# pitching_v3.net
KiCad netlist of a schematic drawn in EAGLE
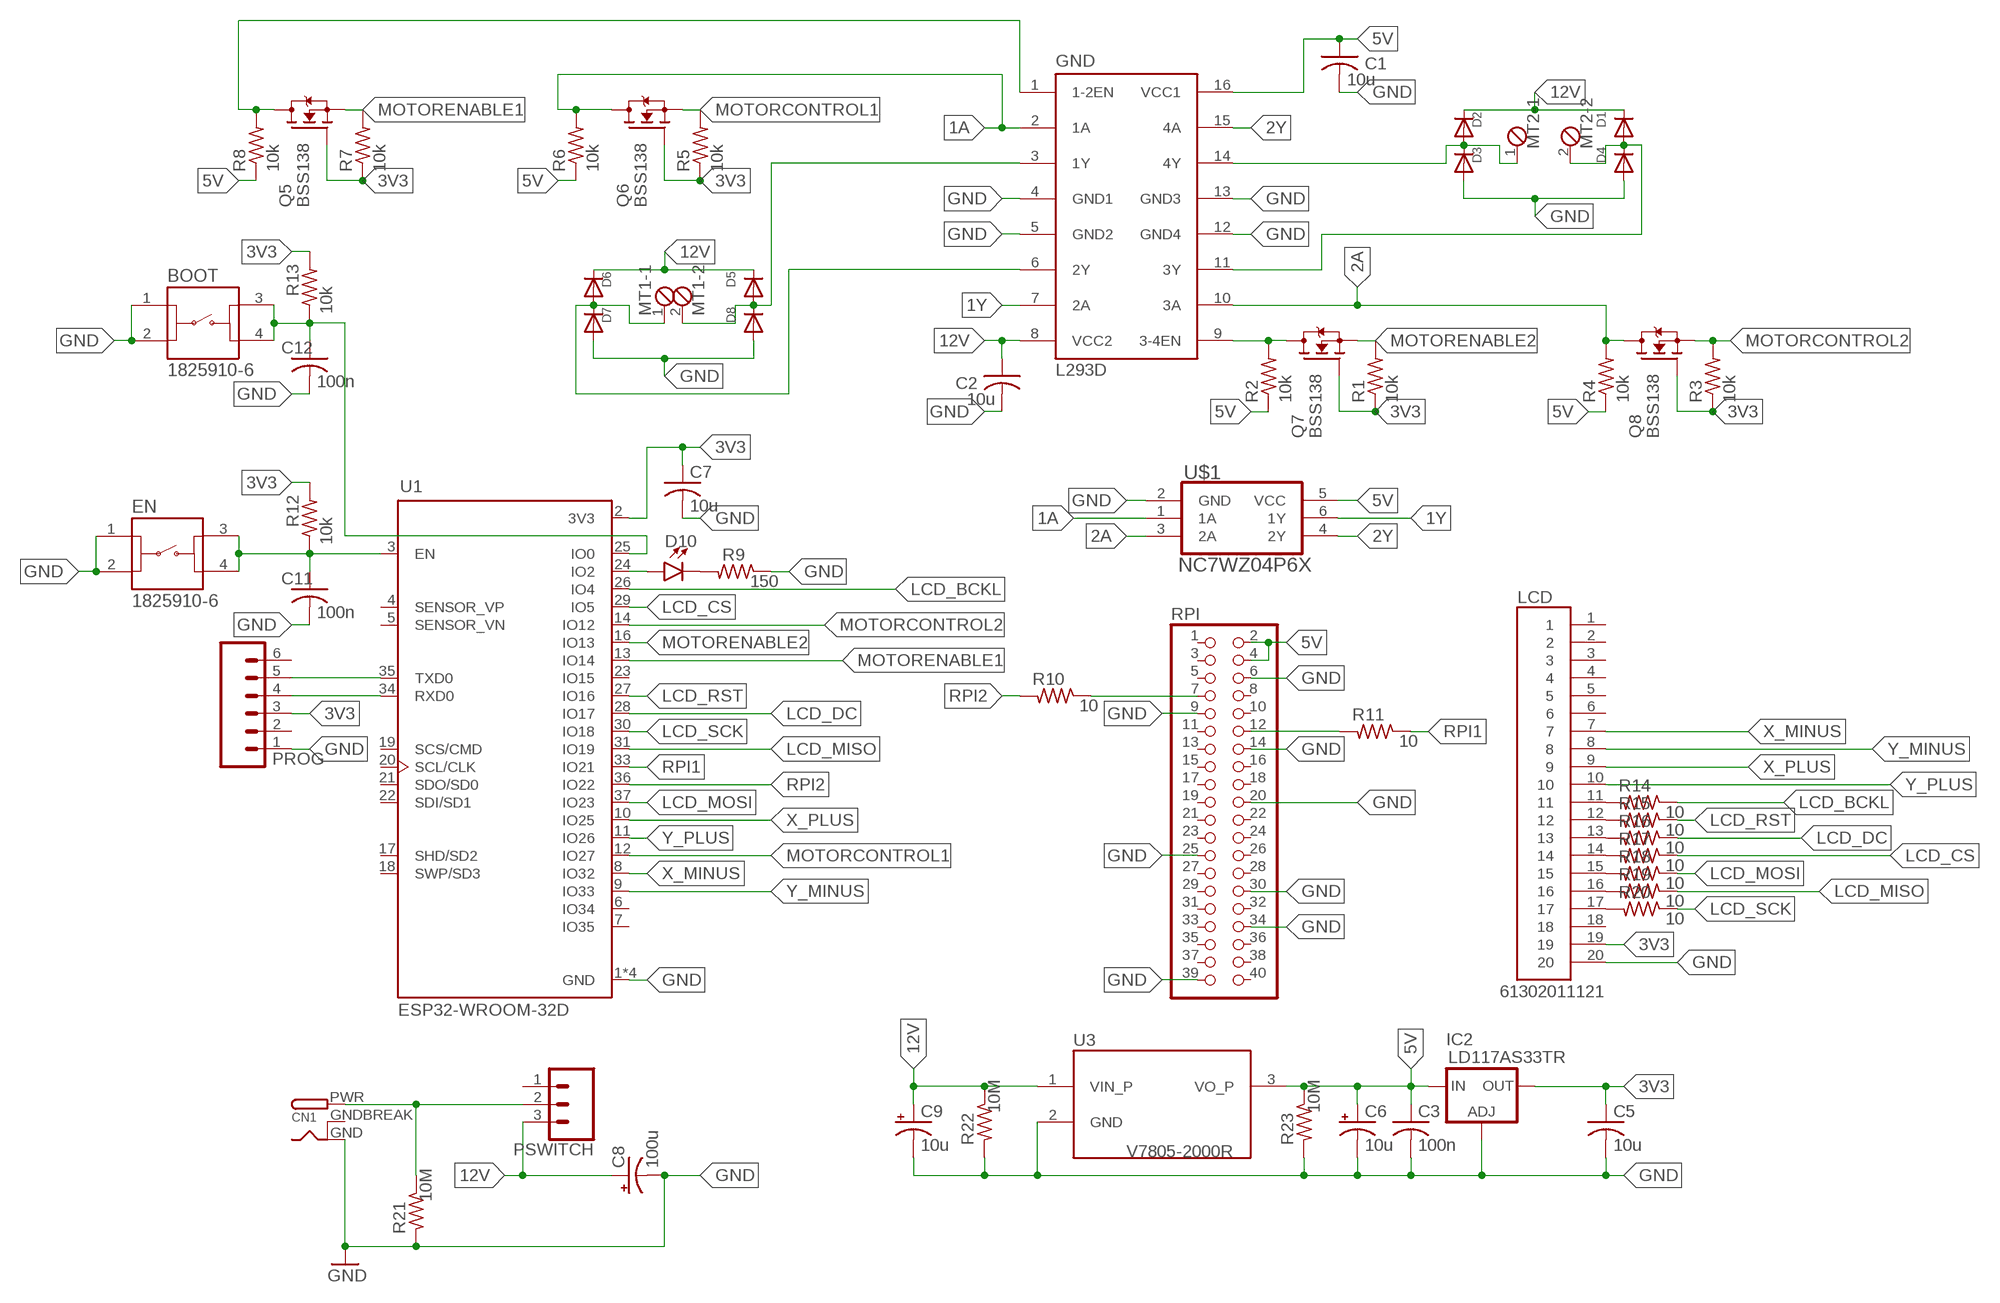
[diagram p0: schematic, sheet 1]

(export (version "E")
  (design (tool "Eeschema 10.0.6"))
  (components
    (comp (ref "BOOT")
      (value "1825910-6")
      (footprint "eagle-import:1825910-6")
      (fields
        (field (name "DIGIKEY_PART_NUMBER") "450-1650-ND")
        (field (name "MANUFACTURER") "TE Connectivity ALCOSWITCH Switches")
        (field (name "CREATED_BY") " PCBLayout.com")
      )
      (libsource (lib "eagle-import") (part "1825910-6"))
    )
    (comp (ref "C1")
      (value "10u")
      (footprint "eagle-import:C0805")
      (libsource (lib "eagle-import") (part "C-USC0805"))
    )
    (comp (ref "C2")
      (value "10u")
      (footprint "eagle-import:C0805")
      (libsource (lib "eagle-import") (part "C-USC0805"))
    )
    (comp (ref "C3")
      (value "100n")
      (footprint "eagle-import:C0805")
      (libsource (lib "eagle-import") (part "C-USC0805"))
    )
    (comp (ref "C5")
      (value "10u")
      (footprint "eagle-import:C0805")
      (libsource (lib "eagle-import") (part "C-USC0805"))
    )
    (comp (ref "C6")
      (value "10u")
      (footprint "eagle-import:153CLV-0405")
      (libsource (lib "eagle-import") (part "CPOL-US153CLV-0405"))
    )
    (comp (ref "C7")
      (value "10u")
      (footprint "eagle-import:C0805")
      (libsource (lib "eagle-import") (part "C-USC0805"))
    )
    (comp (ref "C8")
      (value "100u")
      (footprint "eagle-import:153CLV-0810")
      (libsource (lib "eagle-import") (part "CPOL-US153CLV-0810"))
    )
    (comp (ref "C9")
      (value "10u")
      (footprint "eagle-import:153CLV-0405")
      (libsource (lib "eagle-import") (part "CPOL-US153CLV-0405"))
    )
    (comp (ref "C11")
      (value "100n")
      (footprint "eagle-import:C0805")
      (libsource (lib "eagle-import") (part "C-USC0805"))
    )
    (comp (ref "C12")
      (value "100n")
      (footprint "eagle-import:C0805")
      (libsource (lib "eagle-import") (part "C-USC0805"))
    )
    (comp (ref "CN1")
      (value "DCBARRELPTH")
      (footprint "eagle-import:DCJACK_2MM_PTH")
      (libsource (lib "eagle-import") (part "DCBARRELPTH"))
    )
    (comp (ref "D1")
      (value "DIODESMA")
      (footprint "eagle-import:SMADIODE")
      (libsource (lib "eagle-import") (part "DIODESMA"))
    )
    (comp (ref "D2")
      (value "DIODESMA")
      (footprint "eagle-import:SMADIODE")
      (libsource (lib "eagle-import") (part "DIODESMA"))
    )
    (comp (ref "D3")
      (value "DIODESMA")
      (footprint "eagle-import:SMADIODE")
      (libsource (lib "eagle-import") (part "DIODESMA"))
    )
    (comp (ref "D4")
      (value "DIODESMA")
      (footprint "eagle-import:SMADIODE")
      (libsource (lib "eagle-import") (part "DIODESMA"))
    )
    (comp (ref "D5")
      (value "DIODESMA")
      (footprint "eagle-import:SMADIODE")
      (libsource (lib "eagle-import") (part "DIODESMA"))
    )
    (comp (ref "D6")
      (value "DIODESMA")
      (footprint "eagle-import:SMADIODE")
      (libsource (lib "eagle-import") (part "DIODESMA"))
    )
    (comp (ref "D7")
      (value "DIODESMA")
      (footprint "eagle-import:SMADIODE")
      (libsource (lib "eagle-import") (part "DIODESMA"))
    )
    (comp (ref "D8")
      (value "DIODESMA")
      (footprint "eagle-import:SMADIODE")
      (libsource (lib "eagle-import") (part "DIODESMA"))
    )
    (comp (ref "D10")
      (value "LED3MM")
      (footprint "eagle-import:LED_3MM")
      (libsource (lib "eagle-import") (part "LED3MM"))
    )
    (comp (ref "EN")
      (value "1825910-6")
      (footprint "eagle-import:1825910-6")
      (fields
        (field (name "DIGIKEY_PART_NUMBER") "450-1650-ND")
        (field (name "MANUFACTURER") "TE Connectivity ALCOSWITCH Switches")
        (field (name "CREATED_BY") " PCBLayout.com")
      )
      (libsource (lib "eagle-import") (part "1825910-6"))
    )
    (comp (ref "GND")
      (value "L293D")
      (footprint "eagle-import:DIL16")
      (libsource (lib "eagle-import") (part "L293D"))
    )
    (comp (ref "IC2")
      (value "LD117AS33TR")
      (footprint "eagle-import:SOT223")
      (libsource (lib "eagle-import") (part "LD117A?S33TR"))
    )
    (comp (ref "LCD")
      (value "61302011121")
      (footprint "eagle-import:61302011121")
      (fields
        (field (name "DIGIKEY_PART_NUMBER") "732-5329-ND")
        (field (name "MANUFACTURER") "Wurth Electronics Inc.")
        (field (name "CREATED_BY") "PCBLayout.com")
      )
      (libsource (lib "eagle-import") (part "61302011121"))
    )
    (comp (ref "MT1")
      (value "MPT2")
      (footprint "eagle-import:2POL254")
      (libsource (lib "eagle-import") (part "MPT2"))
    )
    (comp (ref "MT2")
      (value "MPT2")
      (footprint "eagle-import:2POL254")
      (libsource (lib "eagle-import") (part "MPT2"))
    )
    (comp (ref "PROG")
      (value "CONN_06SILK_FEMALE_PTH")
      (footprint "eagle-import:1X06")
      (libsource (lib "eagle-import") (part "CONN_06SILK_FEMALE_PTH"))
    )
    (comp (ref "PSWITCH")
      (value "CONN_03")
      (footprint "eagle-import:1X03")
      (libsource (lib "eagle-import") (part "CONN_03"))
    )
    (comp (ref "Q5")
      (value "BSS138")
      (footprint "eagle-import:SOT23")
      (fields (field (name "MF") "Fairchild"))
      (libsource (lib "eagle-import") (part "BSS138"))
    )
    (comp (ref "Q6")
      (value "BSS138")
      (footprint "eagle-import:SOT23")
      (fields (field (name "MF") "Fairchild"))
      (libsource (lib "eagle-import") (part "BSS138"))
    )
    (comp (ref "Q7")
      (value "BSS138")
      (footprint "eagle-import:SOT23")
      (fields (field (name "MF") "Fairchild"))
      (libsource (lib "eagle-import") (part "BSS138"))
    )
    (comp (ref "Q8")
      (value "BSS138")
      (footprint "eagle-import:SOT23")
      (fields (field (name "MF") "Fairchild"))
      (libsource (lib "eagle-import") (part "BSS138"))
    )
    (comp (ref "R1")
      (value "10k")
      (footprint "eagle-import:R0805")
      (libsource (lib "eagle-import") (part "R-US_R0805"))
    )
    (comp (ref "R2")
      (value "10k")
      (footprint "eagle-import:R0805")
      (libsource (lib "eagle-import") (part "R-US_R0805"))
    )
    (comp (ref "R3")
      (value "10k")
      (footprint "eagle-import:R0805")
      (libsource (lib "eagle-import") (part "R-US_R0805"))
    )
    (comp (ref "R4")
      (value "10k")
      (footprint "eagle-import:R0805")
      (libsource (lib "eagle-import") (part "R-US_R0805"))
    )
    (comp (ref "R5")
      (value "10k")
      (footprint "eagle-import:R0805")
      (libsource (lib "eagle-import") (part "R-US_R0805"))
    )
    (comp (ref "R6")
      (value "10k")
      (footprint "eagle-import:R0805")
      (libsource (lib "eagle-import") (part "R-US_R0805"))
    )
    (comp (ref "R7")
      (value "10k")
      (footprint "eagle-import:R0805")
      (libsource (lib "eagle-import") (part "R-US_R0805"))
    )
    (comp (ref "R8")
      (value "10k")
      (footprint "eagle-import:R0805")
      (libsource (lib "eagle-import") (part "R-US_R0805"))
    )
    (comp (ref "R9")
      (value "150")
      (footprint "eagle-import:R0805")
      (libsource (lib "eagle-import") (part "R-US_R0805"))
    )
    (comp (ref "R10")
      (value "10")
      (footprint "eagle-import:R0805")
      (libsource (lib "eagle-import") (part "R-US_R0805"))
    )
    (comp (ref "R11")
      (value "10")
      (footprint "eagle-import:R0805")
      (libsource (lib "eagle-import") (part "R-US_R0805"))
    )
    (comp (ref "R12")
      (value "10k")
      (footprint "eagle-import:R0805")
      (libsource (lib "eagle-import") (part "R-US_R0805"))
    )
    (comp (ref "R13")
      (value "10k")
      (footprint "eagle-import:R0805")
      (libsource (lib "eagle-import") (part "R-US_R0805"))
    )
    (comp (ref "R14")
      (value "10")
      (footprint "eagle-import:R0805")
      (libsource (lib "eagle-import") (part "R-US_R0805"))
    )
    (comp (ref "R15")
      (value "10")
      (footprint "eagle-import:R0805")
      (libsource (lib "eagle-import") (part "R-US_R0805"))
    )
    (comp (ref "R16")
      (value "10")
      (footprint "eagle-import:R0805")
      (libsource (lib "eagle-import") (part "R-US_R0805"))
    )
    (comp (ref "R17")
      (value "10")
      (footprint "eagle-import:R0805")
      (libsource (lib "eagle-import") (part "R-US_R0805"))
    )
    (comp (ref "R18")
      (value "10")
      (footprint "eagle-import:R0805")
      (libsource (lib "eagle-import") (part "R-US_R0805"))
    )
    (comp (ref "R19")
      (value "10")
      (footprint "eagle-import:R0805")
      (libsource (lib "eagle-import") (part "R-US_R0805"))
    )
    (comp (ref "R20")
      (value "10")
      (footprint "eagle-import:R0805")
      (libsource (lib "eagle-import") (part "R-US_R0805"))
    )
    (comp (ref "R21")
      (value "10M")
      (footprint "eagle-import:R1206")
      (libsource (lib "eagle-import") (part "R-US_R1206"))
    )
    (comp (ref "R22")
      (value "10M")
      (footprint "eagle-import:R1206")
      (libsource (lib "eagle-import") (part "R-US_R1206"))
    )
    (comp (ref "R23")
      (value "10M")
      (footprint "eagle-import:R1206")
      (libsource (lib "eagle-import") (part "R-US_R1206"))
    )
    (comp (ref "RPI")
      (value "PINHD-2X20")
      (footprint "eagle-import:2X20")
      (libsource (lib "eagle-import") (part "PINHD-2X20"))
    )
    (comp (ref "U$1")
      (value "NC7WZ04P6X")
      (footprint "eagle-import:SOT65P210X110-6N")
      (libsource (lib "eagle-import") (part "NC7WZ04P6X"))
    )
    (comp (ref "U1")
      (value "ESP32-WROOM-32D")
      (footprint "eagle-import:MODULE_ESP32-WROOM-32D")
      (fields (field (name "MF") "Espressif Systems"))
      (libsource (lib "eagle-import") (part "ESP32-WROOM-32D"))
    )
    (comp (ref "U3")
      (value "V7805-2000R")
      (footprint "eagle-import:CONV_V7805-2000R")
      (fields (field (name "MANUFACTURER") "CUI INC"))
      (libsource (lib "eagle-import") (part "V7805-2000R"))
    )
  )
  (nets
    (net (code "1") (name "/GNDBREAK") (class "Default")
      (node (ref "CN1") (pin "GNDBREAK") (pinfunction "GNDBREAK_GNDBREAK") (pintype "power_in"))
    )
    (net (code "2") (name "1A") (class "Default")
      (node (ref "GND") (pin "2") (pinfunction "1A_2") (pintype "input"))
      (node (ref "Q6") (pin "3") (pinfunction "D_3") (pintype "passive"))
      (node (ref "R6") (pin "2") (pinfunction "2_2") (pintype "passive"))
      (node (ref "U$1") (pin "1") (pinfunction "1A_1") (pintype "passive"))
    )
    (net (code "3") (name "1Y") (class "Default")
      (node (ref "GND") (pin "7") (pinfunction "2A_7") (pintype "input"))
      (node (ref "U$1") (pin "6") (pinfunction "1Y_6") (pintype "passive"))
    )
    (net (code "4") (name "2A") (class "Default")
      (node (ref "GND") (pin "10") (pinfunction "3A_10") (pintype "input"))
      (node (ref "Q8") (pin "3") (pinfunction "D_3") (pintype "passive"))
      (node (ref "R4") (pin "2") (pinfunction "2_2") (pintype "passive"))
      (node (ref "U$1") (pin "3") (pinfunction "2A_3") (pintype "passive"))
    )
    (net (code "5") (name "2Y") (class "Default")
      (node (ref "GND") (pin "15") (pinfunction "4A_15") (pintype "input"))
      (node (ref "U$1") (pin "4") (pinfunction "2Y_4") (pintype "passive"))
    )
    (net (code "6") (name "3V3") (class "Default")
      (node (ref "C5") (pin "1") (pinfunction "1_1") (pintype "passive"))
      (node (ref "C7") (pin "1") (pinfunction "1_1") (pintype "passive"))
      (node (ref "IC2") (pin "4") (pinfunction "OUT_4") (pintype "passive"))
      (node (ref "LCD") (pin "19") (pinfunction "19_19") (pintype "passive"))
      (node (ref "PROG") (pin "3") (pinfunction "3_3") (pintype "passive"))
      (node (ref "Q5") (pin "1") (pinfunction "G_1") (pintype "passive"))
      (node (ref "Q6") (pin "1") (pinfunction "G_1") (pintype "passive"))
      (node (ref "Q7") (pin "1") (pinfunction "G_1") (pintype "passive"))
      (node (ref "Q8") (pin "1") (pinfunction "G_1") (pintype "passive"))
      (node (ref "R1") (pin "1") (pinfunction "1_1") (pintype "passive"))
      (node (ref "R12") (pin "2") (pinfunction "2_2") (pintype "passive"))
      (node (ref "R13") (pin "2") (pinfunction "2_2") (pintype "passive"))
      (node (ref "R3") (pin "1") (pinfunction "1_1") (pintype "passive"))
      (node (ref "R5") (pin "1") (pinfunction "1_1") (pintype "passive"))
      (node (ref "R7") (pin "1") (pinfunction "1_1") (pintype "passive"))
      (node (ref "U1") (pin "2") (pinfunction "3V3_2") (pintype "power_in"))
    )
    (net (code "7") (name "5V") (class "Default")
      (node (ref "C1") (pin "1") (pinfunction "1_1") (pintype "passive"))
      (node (ref "C3") (pin "1") (pinfunction "1_1") (pintype "passive"))
      (node (ref "C6") (pin "+") (pinfunction "+_+") (pintype "passive"))
      (node (ref "GND") (pin "16") (pinfunction "VCC1_16") (pintype "power_in"))
      (node (ref "IC2") (pin "3") (pinfunction "IN_3") (pintype "input"))
      (node (ref "R2") (pin "1") (pinfunction "1_1") (pintype "passive"))
      (node (ref "R23") (pin "1") (pinfunction "1_1") (pintype "passive"))
      (node (ref "R4") (pin "1") (pinfunction "1_1") (pintype "passive"))
      (node (ref "R6") (pin "1") (pinfunction "1_1") (pintype "passive"))
      (node (ref "R8") (pin "1") (pinfunction "1_1") (pintype "passive"))
      (node (ref "RPI") (pin "2") (pinfunction "2_2") (pintype "passive"))
      (node (ref "RPI") (pin "4") (pinfunction "4_4") (pintype "passive"))
      (node (ref "U$1") (pin "5") (pinfunction "VCC_5") (pintype "passive"))
      (node (ref "U3") (pin "3") (pinfunction "VO_P_3") (pintype "output"))
    )
    (net (code "8") (name "12V") (class "Default")
      (node (ref "C2") (pin "1") (pinfunction "1_1") (pintype "passive"))
      (node (ref "C8") (pin "+") (pinfunction "+_+") (pintype "passive"))
      (node (ref "C9") (pin "+") (pinfunction "+_+") (pintype "passive"))
      (node (ref "D1") (pin "C") (pinfunction "C_C") (pintype "passive"))
      (node (ref "D2") (pin "C") (pinfunction "C_C") (pintype "passive"))
      (node (ref "D5") (pin "C") (pinfunction "C_C") (pintype "passive"))
      (node (ref "D6") (pin "C") (pinfunction "C_C") (pintype "passive"))
      (node (ref "GND") (pin "8") (pinfunction "VCC2_8") (pintype "power_in"))
      (node (ref "PSWITCH") (pin "3") (pinfunction "3_3") (pintype "passive"))
      (node (ref "R22") (pin "1") (pinfunction "1_1") (pintype "passive"))
      (node (ref "U3") (pin "1") (pinfunction "VIN_P_1") (pintype "input"))
    )
    (net (code "9") (name "GND") (class "Default")
      (node (ref "BOOT") (pin "1") (pinfunction "1_1") (pintype "passive"))
      (node (ref "BOOT") (pin "2") (pinfunction "2_2") (pintype "passive"))
      (node (ref "C1") (pin "2") (pinfunction "2_2") (pintype "passive"))
      (node (ref "C11") (pin "2") (pinfunction "2_2") (pintype "passive"))
      (node (ref "C12") (pin "2") (pinfunction "2_2") (pintype "passive"))
      (node (ref "C2") (pin "2") (pinfunction "2_2") (pintype "passive"))
      (node (ref "C3") (pin "2") (pinfunction "2_2") (pintype "passive"))
      (node (ref "C5") (pin "2") (pinfunction "2_2") (pintype "passive"))
      (node (ref "C6") (pin "-") (pinfunction "-_-") (pintype "passive"))
      (node (ref "C7") (pin "2") (pinfunction "2_2") (pintype "passive"))
      (node (ref "C8") (pin "-") (pinfunction "-_-") (pintype "passive"))
      (node (ref "C9") (pin "-") (pinfunction "-_-") (pintype "passive"))
      (node (ref "CN1") (pin "GND") (pinfunction "GND_GND") (pintype "power_in"))
      (node (ref "D3") (pin "A") (pinfunction "A_A") (pintype "passive"))
      (node (ref "D4") (pin "A") (pinfunction "A_A") (pintype "passive"))
      (node (ref "D7") (pin "A") (pinfunction "A_A") (pintype "passive"))
      (node (ref "D8") (pin "A") (pinfunction "A_A") (pintype "passive"))
      (node (ref "EN") (pin "1") (pinfunction "1_1") (pintype "passive"))
      (node (ref "EN") (pin "2") (pinfunction "2_2") (pintype "passive"))
      (node (ref "GND") (pin "12") (pinfunction "GND4_12") (pintype "power_in"))
      (node (ref "GND") (pin "13") (pinfunction "GND3_13") (pintype "power_in"))
      (node (ref "GND") (pin "4") (pinfunction "GND1_4") (pintype "power_in"))
      (node (ref "GND") (pin "5") (pinfunction "GND2_5") (pintype "power_in"))
      (node (ref "IC2") (pin "1") (pinfunction "ADJ_1") (pintype "input"))
      (node (ref "LCD") (pin "20") (pinfunction "20_20") (pintype "passive"))
      (node (ref "PROG") (pin "1") (pinfunction "1_1") (pintype "passive"))
      (node (ref "R21") (pin "2") (pinfunction "2_2") (pintype "passive"))
      (node (ref "R22") (pin "2") (pinfunction "2_2") (pintype "passive"))
      (node (ref "R23") (pin "2") (pinfunction "2_2") (pintype "passive"))
      (node (ref "R9") (pin "1") (pinfunction "1_1") (pintype "passive"))
      (node (ref "RPI") (pin "14") (pinfunction "14_14") (pintype "passive"))
      (node (ref "RPI") (pin "20") (pinfunction "20_20") (pintype "passive"))
      (node (ref "RPI") (pin "25") (pinfunction "25_25") (pintype "passive"))
      (node (ref "RPI") (pin "30") (pinfunction "30_30") (pintype "passive"))
      (node (ref "RPI") (pin "34") (pinfunction "34_34") (pintype "passive"))
      (node (ref "RPI") (pin "39") (pinfunction "39_39") (pintype "passive"))
      (node (ref "RPI") (pin "6") (pinfunction "6_6") (pintype "passive"))
      (node (ref "RPI") (pin "9") (pinfunction "9_9") (pintype "passive"))
      (node (ref "U$1") (pin "2") (pinfunction "GND_2") (pintype "passive"))
      (node (ref "U1") (pin "1") (pinfunction "GND_1") (pintype "power_in"))
      (node (ref "U1") (pin "15") (pinfunction "GND_15") (pintype "power_in"))
      (node (ref "U1") (pin "38") (pinfunction "GND_38") (pintype "power_in"))
      (node (ref "U1") (pin "39") (pinfunction "GND_39") (pintype "power_in"))
      (node (ref "U3") (pin "2") (pinfunction "GND_2") (pintype "power_in"))
    )
    (net (code "10") (name "LCD_BCKL") (class "Default")
      (node (ref "R14") (pin "1") (pinfunction "1_1") (pintype "passive"))
      (node (ref "U1") (pin "26") (pinfunction "IO4_26") (pintype "bidirectional"))
    )
    (net (code "11") (name "LCD_CS") (class "Default")
      (node (ref "R17") (pin "1") (pinfunction "1_1") (pintype "passive"))
      (node (ref "U1") (pin "29") (pinfunction "IO5_29") (pintype "bidirectional"))
    )
    (net (code "12") (name "LCD_DC") (class "Default")
      (node (ref "R16") (pin "1") (pinfunction "1_1") (pintype "passive"))
      (node (ref "U1") (pin "28") (pinfunction "IO17_28") (pintype "bidirectional"))
    )
    (net (code "13") (name "LCD_MISO") (class "Default")
      (node (ref "R19") (pin "1") (pinfunction "1_1") (pintype "passive"))
      (node (ref "U1") (pin "31") (pinfunction "IO19_31") (pintype "bidirectional"))
    )
    (net (code "14") (name "LCD_MOSI") (class "Default")
      (node (ref "R18") (pin "1") (pinfunction "1_1") (pintype "passive"))
      (node (ref "U1") (pin "37") (pinfunction "IO23_37") (pintype "bidirectional"))
    )
    (net (code "15") (name "LCD_RST") (class "Default")
      (node (ref "R15") (pin "1") (pinfunction "1_1") (pintype "passive"))
      (node (ref "U1") (pin "27") (pinfunction "IO16_27") (pintype "bidirectional"))
    )
    (net (code "16") (name "LCD_SCK") (class "Default")
      (node (ref "R20") (pin "1") (pinfunction "1_1") (pintype "passive"))
      (node (ref "U1") (pin "30") (pinfunction "IO18_30") (pintype "bidirectional"))
    )
    (net (code "17") (name "MOTORCONTROL1") (class "Default")
      (node (ref "Q6") (pin "2") (pinfunction "S_2") (pintype "passive"))
      (node (ref "R5") (pin "2") (pinfunction "2_2") (pintype "passive"))
      (node (ref "U1") (pin "12") (pinfunction "IO27_12") (pintype "bidirectional"))
    )
    (net (code "18") (name "MOTORCONTROL2") (class "Default")
      (node (ref "Q8") (pin "2") (pinfunction "S_2") (pintype "passive"))
      (node (ref "R3") (pin "2") (pinfunction "2_2") (pintype "passive"))
      (node (ref "U1") (pin "14") (pinfunction "IO12_14") (pintype "bidirectional"))
    )
    (net (code "19") (name "MOTORENABLE1") (class "Default")
      (node (ref "Q5") (pin "2") (pinfunction "S_2") (pintype "passive"))
      (node (ref "R7") (pin "2") (pinfunction "2_2") (pintype "passive"))
      (node (ref "U1") (pin "13") (pinfunction "IO14_13") (pintype "bidirectional"))
    )
    (net (code "20") (name "MOTORENABLE2") (class "Default")
      (node (ref "Q7") (pin "2") (pinfunction "S_2") (pintype "passive"))
      (node (ref "R1") (pin "2") (pinfunction "2_2") (pintype "passive"))
      (node (ref "U1") (pin "16") (pinfunction "IO13_16") (pintype "bidirectional"))
    )
    (net (code "21") (name "Net-(CN1-PadPWR)") (class "Default")
      (node (ref "CN1") (pin "PWR") (pinfunction "PWR_PWR") (pintype "power_in"))
      (node (ref "PSWITCH") (pin "2") (pinfunction "2_2") (pintype "passive"))
      (node (ref "R21") (pin "1") (pinfunction "1_1") (pintype "passive"))
    )
    (net (code "22") (name "Net-(D10-C)") (class "Default")
      (node (ref "D10") (pin "K") (pinfunction "C_K") (pintype "passive"))
      (node (ref "R9") (pin "2") (pinfunction "2_2") (pintype "passive"))
    )
    (net (code "23") (name "Net-(GND-1-2EN)") (class "Default")
      (node (ref "GND") (pin "1") (pinfunction "1-2EN_1") (pintype "input"))
      (node (ref "Q5") (pin "3") (pinfunction "D_3") (pintype "passive"))
      (node (ref "R8") (pin "2") (pinfunction "2_2") (pintype "passive"))
    )
    (net (code "24") (name "Net-(GND-1Y)") (class "Default")
      (node (ref "D5") (pin "A") (pinfunction "A_A") (pintype "passive"))
      (node (ref "D8") (pin "C") (pinfunction "C_C") (pintype "passive"))
      (node (ref "GND") (pin "3") (pinfunction "1Y_3") (pintype "output"))
      (node (ref "MT1") (pin "2") (pinfunction "1_2") (pintype "passive"))
    )
    (net (code "25") (name "Net-(GND-2Y)") (class "Default")
      (node (ref "D6") (pin "A") (pinfunction "A_A") (pintype "passive"))
      (node (ref "D7") (pin "C") (pinfunction "C_C") (pintype "passive"))
      (node (ref "GND") (pin "6") (pinfunction "2Y_6") (pintype "output"))
      (node (ref "MT1") (pin "1") (pinfunction "1_1") (pintype "passive"))
    )
    (net (code "26") (name "Net-(GND-3-4EN)") (class "Default")
      (node (ref "GND") (pin "9") (pinfunction "3-4EN_9") (pintype "input"))
      (node (ref "Q7") (pin "3") (pinfunction "D_3") (pintype "passive"))
      (node (ref "R2") (pin "2") (pinfunction "2_2") (pintype "passive"))
    )
    (net (code "27") (name "Net-(GND-3Y)") (class "Default")
      (node (ref "D1") (pin "A") (pinfunction "A_A") (pintype "passive"))
      (node (ref "D4") (pin "C") (pinfunction "C_C") (pintype "passive"))
      (node (ref "GND") (pin "11") (pinfunction "3Y_11") (pintype "output"))
      (node (ref "MT2") (pin "2") (pinfunction "1_2") (pintype "passive"))
    )
    (net (code "28") (name "Net-(GND-4Y)") (class "Default")
      (node (ref "D2") (pin "A") (pinfunction "A_A") (pintype "passive"))
      (node (ref "D3") (pin "C") (pinfunction "C_C") (pintype "passive"))
      (node (ref "GND") (pin "14") (pinfunction "4Y_14") (pintype "output"))
      (node (ref "MT2") (pin "1") (pinfunction "1_1") (pintype "passive"))
    )
    (net (code "29") (name "Net-(LCD-Pad11)") (class "Default")
      (node (ref "LCD") (pin "11") (pinfunction "11_11") (pintype "passive"))
      (node (ref "R14") (pin "2") (pinfunction "2_2") (pintype "passive"))
    )
    (net (code "30") (name "Net-(LCD-Pad12)") (class "Default")
      (node (ref "LCD") (pin "12") (pinfunction "12_12") (pintype "passive"))
      (node (ref "R15") (pin "2") (pinfunction "2_2") (pintype "passive"))
    )
    (net (code "31") (name "Net-(LCD-Pad13)") (class "Default")
      (node (ref "LCD") (pin "13") (pinfunction "13_13") (pintype "passive"))
      (node (ref "R16") (pin "2") (pinfunction "2_2") (pintype "passive"))
    )
    (net (code "32") (name "Net-(LCD-Pad14)") (class "Default")
      (node (ref "LCD") (pin "14") (pinfunction "14_14") (pintype "passive"))
      (node (ref "R17") (pin "2") (pinfunction "2_2") (pintype "passive"))
    )
    (net (code "33") (name "Net-(LCD-Pad15)") (class "Default")
      (node (ref "LCD") (pin "15") (pinfunction "15_15") (pintype "passive"))
      (node (ref "R18") (pin "2") (pinfunction "2_2") (pintype "passive"))
    )
    (net (code "34") (name "Net-(LCD-Pad16)") (class "Default")
      (node (ref "LCD") (pin "16") (pinfunction "16_16") (pintype "passive"))
      (node (ref "R19") (pin "2") (pinfunction "2_2") (pintype "passive"))
    )
    (net (code "35") (name "Net-(LCD-Pad17)") (class "Default")
      (node (ref "LCD") (pin "17") (pinfunction "17_17") (pintype "passive"))
      (node (ref "R20") (pin "2") (pinfunction "2_2") (pintype "passive"))
    )
    (net (code "36") (name "Net-(R10-Pad1)") (class "Default")
      (node (ref "R10") (pin "1") (pinfunction "1_1") (pintype "passive"))
      (node (ref "RPI") (pin "7") (pinfunction "7_7") (pintype "passive"))
    )
    (net (code "37") (name "Net-(R11-Pad2)") (class "Default")
      (node (ref "R11") (pin "2") (pinfunction "2_2") (pintype "passive"))
      (node (ref "RPI") (pin "12") (pinfunction "12_12") (pintype "passive"))
    )
    (net (code "38") (name "Net-(U1-EN)") (class "Default")
      (node (ref "C11") (pin "1") (pinfunction "1_1") (pintype "passive"))
      (node (ref "EN") (pin "3") (pinfunction "3_3") (pintype "passive"))
      (node (ref "EN") (pin "4") (pinfunction "4_4") (pintype "passive"))
      (node (ref "R12") (pin "1") (pinfunction "1_1") (pintype "passive"))
      (node (ref "U1") (pin "3") (pinfunction "EN_3") (pintype "input"))
    )
    (net (code "39") (name "Net-(U1-IO0)") (class "Default")
      (node (ref "BOOT") (pin "3") (pinfunction "3_3") (pintype "passive"))
      (node (ref "BOOT") (pin "4") (pinfunction "4_4") (pintype "passive"))
      (node (ref "C12") (pin "1") (pinfunction "1_1") (pintype "passive"))
      (node (ref "R13") (pin "1") (pinfunction "1_1") (pintype "passive"))
      (node (ref "U1") (pin "25") (pinfunction "IO0_25") (pintype "bidirectional"))
    )
    (net (code "40") (name "Net-(U1-IO2)") (class "Default")
      (node (ref "D10") (pin "A") (pinfunction "A_A") (pintype "passive"))
      (node (ref "U1") (pin "24") (pinfunction "IO2_24") (pintype "bidirectional"))
    )
    (net (code "41") (name "Net-(U1-RXD0)") (class "Default")
      (node (ref "PROG") (pin "4") (pinfunction "4_4") (pintype "passive"))
      (node (ref "U1") (pin "34") (pinfunction "RXD0_34") (pintype "bidirectional"))
    )
    (net (code "42") (name "Net-(U1-TXD0)") (class "Default")
      (node (ref "PROG") (pin "5") (pinfunction "5_5") (pintype "passive"))
      (node (ref "U1") (pin "35") (pinfunction "TXD0_35") (pintype "bidirectional"))
    )
    (net (code "43") (name "RPI1") (class "Default")
      (node (ref "R11") (pin "1") (pinfunction "1_1") (pintype "passive"))
      (node (ref "U1") (pin "33") (pinfunction "IO21_33") (pintype "bidirectional"))
    )
    (net (code "44") (name "RPI2") (class "Default")
      (node (ref "R10") (pin "2") (pinfunction "2_2") (pintype "passive"))
      (node (ref "U1") (pin "36") (pinfunction "IO22_36") (pintype "bidirectional"))
    )
    (net (code "45") (name "X_MINUS") (class "Default")
      (node (ref "LCD") (pin "7") (pinfunction "7_7") (pintype "passive"))
      (node (ref "U1") (pin "8") (pinfunction "IO32_8") (pintype "bidirectional"))
    )
    (net (code "46") (name "X_PLUS") (class "Default")
      (node (ref "LCD") (pin "9") (pinfunction "9_9") (pintype "passive"))
      (node (ref "U1") (pin "10") (pinfunction "IO25_10") (pintype "bidirectional"))
    )
    (net (code "47") (name "Y_MINUS") (class "Default")
      (node (ref "LCD") (pin "8") (pinfunction "8_8") (pintype "passive"))
      (node (ref "U1") (pin "9") (pinfunction "IO33_9") (pintype "bidirectional"))
    )
    (net (code "48") (name "Y_PLUS") (class "Default")
      (node (ref "LCD") (pin "10") (pinfunction "10_10") (pintype "passive"))
      (node (ref "U1") (pin "11") (pinfunction "IO26_11") (pintype "bidirectional"))
    )
    (net (code "49") (name "unconnected-(LCD-Pad1)") (class "Default")
      (node (ref "LCD") (pin "1") (pinfunction "1_1") (pintype "passive"))
    )
    (net (code "50") (name "unconnected-(LCD-Pad2)") (class "Default")
      (node (ref "LCD") (pin "2") (pinfunction "2_2") (pintype "passive"))
    )
    (net (code "51") (name "unconnected-(LCD-Pad3)") (class "Default")
      (node (ref "LCD") (pin "3") (pinfunction "3_3") (pintype "passive"))
    )
    (net (code "52") (name "unconnected-(LCD-Pad4)") (class "Default")
      (node (ref "LCD") (pin "4") (pinfunction "4_4") (pintype "passive"))
    )
    (net (code "53") (name "unconnected-(LCD-Pad5)") (class "Default")
      (node (ref "LCD") (pin "5") (pinfunction "5_5") (pintype "passive"))
    )
    (net (code "54") (name "unconnected-(LCD-Pad6)") (class "Default")
      (node (ref "LCD") (pin "6") (pinfunction "6_6") (pintype "passive"))
    )
    (net (code "55") (name "unconnected-(LCD-Pad18)") (class "Default")
      (node (ref "LCD") (pin "18") (pinfunction "18_18") (pintype "passive"))
    )
    (net (code "56") (name "unconnected-(PROG-Pad2)") (class "Default")
      (node (ref "PROG") (pin "2") (pinfunction "2_2") (pintype "passive"))
    )
    (net (code "57") (name "unconnected-(PROG-Pad6)") (class "Default")
      (node (ref "PROG") (pin "6") (pinfunction "6_6") (pintype "passive"))
    )
    (net (code "58") (name "unconnected-(PSWITCH-Pad1)") (class "Default")
      (node (ref "PSWITCH") (pin "1") (pinfunction "1_1") (pintype "passive"))
    )
    (net (code "59") (name "unconnected-(RPI-Pad1)") (class "Default")
      (node (ref "RPI") (pin "1") (pinfunction "1_1") (pintype "passive"))
    )
    (net (code "60") (name "unconnected-(RPI-Pad3)") (class "Default")
      (node (ref "RPI") (pin "3") (pinfunction "3_3") (pintype "passive"))
    )
    (net (code "61") (name "unconnected-(RPI-Pad5)") (class "Default")
      (node (ref "RPI") (pin "5") (pinfunction "5_5") (pintype "passive"))
    )
    (net (code "62") (name "unconnected-(RPI-Pad8)") (class "Default")
      (node (ref "RPI") (pin "8") (pinfunction "8_8") (pintype "passive"))
    )
    (net (code "63") (name "unconnected-(RPI-Pad10)") (class "Default")
      (node (ref "RPI") (pin "10") (pinfunction "10_10") (pintype "passive"))
    )
    (net (code "64") (name "unconnected-(RPI-Pad11)") (class "Default")
      (node (ref "RPI") (pin "11") (pinfunction "11_11") (pintype "passive"))
    )
    (net (code "65") (name "unconnected-(RPI-Pad13)") (class "Default")
      (node (ref "RPI") (pin "13") (pinfunction "13_13") (pintype "passive"))
    )
    (net (code "66") (name "unconnected-(RPI-Pad15)") (class "Default")
      (node (ref "RPI") (pin "15") (pinfunction "15_15") (pintype "passive"))
    )
    (net (code "67") (name "unconnected-(RPI-Pad16)") (class "Default")
      (node (ref "RPI") (pin "16") (pinfunction "16_16") (pintype "passive"))
    )
    (net (code "68") (name "unconnected-(RPI-Pad17)") (class "Default")
      (node (ref "RPI") (pin "17") (pinfunction "17_17") (pintype "passive"))
    )
    (net (code "69") (name "unconnected-(RPI-Pad18)") (class "Default")
      (node (ref "RPI") (pin "18") (pinfunction "18_18") (pintype "passive"))
    )
    (net (code "70") (name "unconnected-(RPI-Pad19)") (class "Default")
      (node (ref "RPI") (pin "19") (pinfunction "19_19") (pintype "passive"))
    )
    (net (code "71") (name "unconnected-(RPI-Pad21)") (class "Default")
      (node (ref "RPI") (pin "21") (pinfunction "21_21") (pintype "passive"))
    )
    (net (code "72") (name "unconnected-(RPI-Pad22)") (class "Default")
      (node (ref "RPI") (pin "22") (pinfunction "22_22") (pintype "passive"))
    )
    (net (code "73") (name "unconnected-(RPI-Pad23)") (class "Default")
      (node (ref "RPI") (pin "23") (pinfunction "23_23") (pintype "passive"))
    )
    (net (code "74") (name "unconnected-(RPI-Pad24)") (class "Default")
      (node (ref "RPI") (pin "24") (pinfunction "24_24") (pintype "passive"))
    )
    (net (code "75") (name "unconnected-(RPI-Pad26)") (class "Default")
      (node (ref "RPI") (pin "26") (pinfunction "26_26") (pintype "passive"))
    )
    (net (code "76") (name "unconnected-(RPI-Pad27)") (class "Default")
      (node (ref "RPI") (pin "27") (pinfunction "27_27") (pintype "passive"))
    )
    (net (code "77") (name "unconnected-(RPI-Pad28)") (class "Default")
      (node (ref "RPI") (pin "28") (pinfunction "28_28") (pintype "passive"))
    )
    (net (code "78") (name "unconnected-(RPI-Pad29)") (class "Default")
      (node (ref "RPI") (pin "29") (pinfunction "29_29") (pintype "passive"))
    )
    (net (code "79") (name "unconnected-(RPI-Pad31)") (class "Default")
      (node (ref "RPI") (pin "31") (pinfunction "31_31") (pintype "passive"))
    )
    (net (code "80") (name "unconnected-(RPI-Pad32)") (class "Default")
      (node (ref "RPI") (pin "32") (pinfunction "32_32") (pintype "passive"))
    )
    (net (code "81") (name "unconnected-(RPI-Pad33)") (class "Default")
      (node (ref "RPI") (pin "33") (pinfunction "33_33") (pintype "passive"))
    )
    (net (code "82") (name "unconnected-(RPI-Pad35)") (class "Default")
      (node (ref "RPI") (pin "35") (pinfunction "35_35") (pintype "passive"))
    )
    (net (code "83") (name "unconnected-(RPI-Pad36)") (class "Default")
      (node (ref "RPI") (pin "36") (pinfunction "36_36") (pintype "passive"))
    )
    (net (code "84") (name "unconnected-(RPI-Pad37)") (class "Default")
      (node (ref "RPI") (pin "37") (pinfunction "37_37") (pintype "passive"))
    )
    (net (code "85") (name "unconnected-(RPI-Pad38)") (class "Default")
      (node (ref "RPI") (pin "38") (pinfunction "38_38") (pintype "passive"))
    )
    (net (code "86") (name "unconnected-(RPI-Pad40)") (class "Default")
      (node (ref "RPI") (pin "40") (pinfunction "40_40") (pintype "passive"))
    )
    (net (code "87") (name "unconnected-(U1-IO15-Pad23)") (class "Default")
      (node (ref "U1") (pin "23") (pinfunction "IO15_23") (pintype "bidirectional"))
    )
    (net (code "88") (name "unconnected-(U1-IO34-Pad6)") (class "Default")
      (node (ref "U1") (pin "6") (pinfunction "IO34_6") (pintype "bidirectional"))
    )
    (net (code "89") (name "unconnected-(U1-IO35-Pad7)") (class "Default")
      (node (ref "U1") (pin "7") (pinfunction "IO35_7") (pintype "bidirectional"))
    )
    (net (code "90") (name "unconnected-(U1-SCL{slash}CLK-Pad20)") (class "Default")
      (node (ref "U1") (pin "20") (pinfunction "SCL/CLK_20") (pintype "bidirectional"))
    )
    (net (code "91") (name "unconnected-(U1-SCS{slash}CMD-Pad19)") (class "Default")
      (node (ref "U1") (pin "19") (pinfunction "SCS/CMD_19") (pintype "bidirectional"))
    )
    (net (code "92") (name "unconnected-(U1-SDI{slash}SD1-Pad22)") (class "Default")
      (node (ref "U1") (pin "22") (pinfunction "SDI/SD1_22") (pintype "bidirectional"))
    )
    (net (code "93") (name "unconnected-(U1-SDO{slash}SD0-Pad21)") (class "Default")
      (node (ref "U1") (pin "21") (pinfunction "SDO/SD0_21") (pintype "bidirectional"))
    )
    (net (code "94") (name "unconnected-(U1-SENSOR_VN-Pad5)") (class "Default")
      (node (ref "U1") (pin "5") (pinfunction "SENSOR_VN_5") (pintype "input"))
    )
    (net (code "95") (name "unconnected-(U1-SENSOR_VP-Pad4)") (class "Default")
      (node (ref "U1") (pin "4") (pinfunction "SENSOR_VP_4") (pintype "input"))
    )
    (net (code "96") (name "unconnected-(U1-SHD{slash}SD2-Pad17)") (class "Default")
      (node (ref "U1") (pin "17") (pinfunction "SHD/SD2_17") (pintype "bidirectional"))
    )
    (net (code "97") (name "unconnected-(U1-SWP{slash}SD3-Pad18)") (class "Default")
      (node (ref "U1") (pin "18") (pinfunction "SWP/SD3_18") (pintype "bidirectional"))
    )
  )
)
